# Part2.net
KiCad netlist of a schematic drawn in Altium Designer
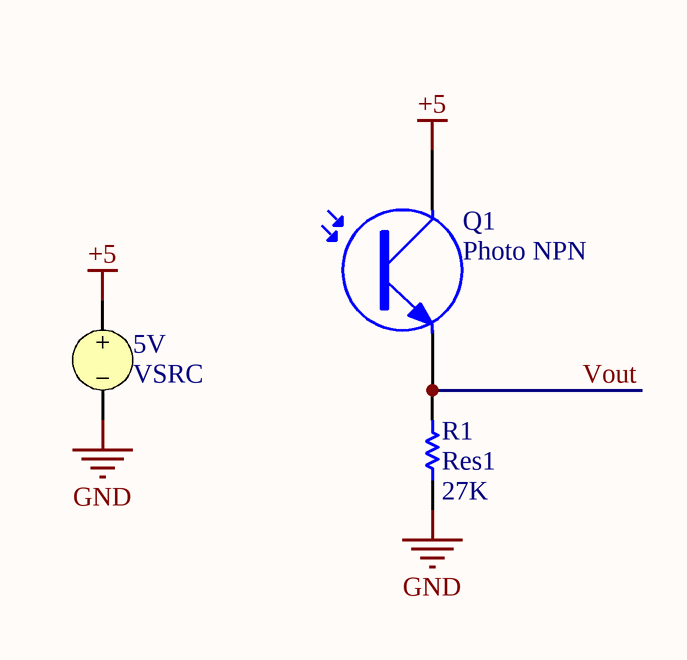
[diagram p0: Part2.SchDoc]

(export (version "E")
  (design (tool "Eeschema 10.0.6"))
  (components
    (comp (ref "5V")
      (value "VSRC")
      (description "Voltage Source")
      (fields (field (name "PUBLISHER") "Altium Limited"))
      (libsource (lib "Simulation Sources") (part "VSRC"))
    )
    (comp (ref "Q1")
      (value "Photo NPN")
      (footprint "SFM-T2(3)/X1.6V")
      (description "NPN Phototransistor")
      (fields (field (name "MANUFACTURER") "Generic Components"))
      (libsource (lib "ME218_BaseLib") (part "Photo NPN"))
    )
    (comp (ref "R1")
      (value "Res1")
      (footprint "AXIAL-0.3")
      (description "Resistor")
      (fields
        (field (name "MANUFACTURER") "Generic Components")
        (field (name "ALTIUM_VALUE") "27K")
        (field (name "PUBLISHER") "Altium Hobart Technology Centre")
      )
      (libsource (lib "ME218_BaseLib") (part "Res1"))
    )
  )
  (nets
    (net (code "1") (name "+5") (class "Default")
      (node (ref "5V") (pin "1") (pinfunction "1_1") (pintype "passive"))
      (node (ref "Q1") (pin "1") (pinfunction "C_1") (pintype "passive"))
    )
    (net (code "2") (name "/Vout") (class "Default")
      (node (ref "Q1") (pin "3") (pinfunction "E_3") (pintype "passive"))
      (node (ref "R1") (pin "2") (pinfunction "2_2") (pintype "passive"))
    )
    (net (code "3") (name "GND") (class "Default")
      (node (ref "5V") (pin "2") (pinfunction "2_2") (pintype "passive"))
      (node (ref "R1") (pin "1") (pinfunction "1_1") (pintype "passive"))
    )
  )
)
